# SCH_FirstPCB_2024-05-11.net
KiCad netlist of a schematic drawn in EasyEDA
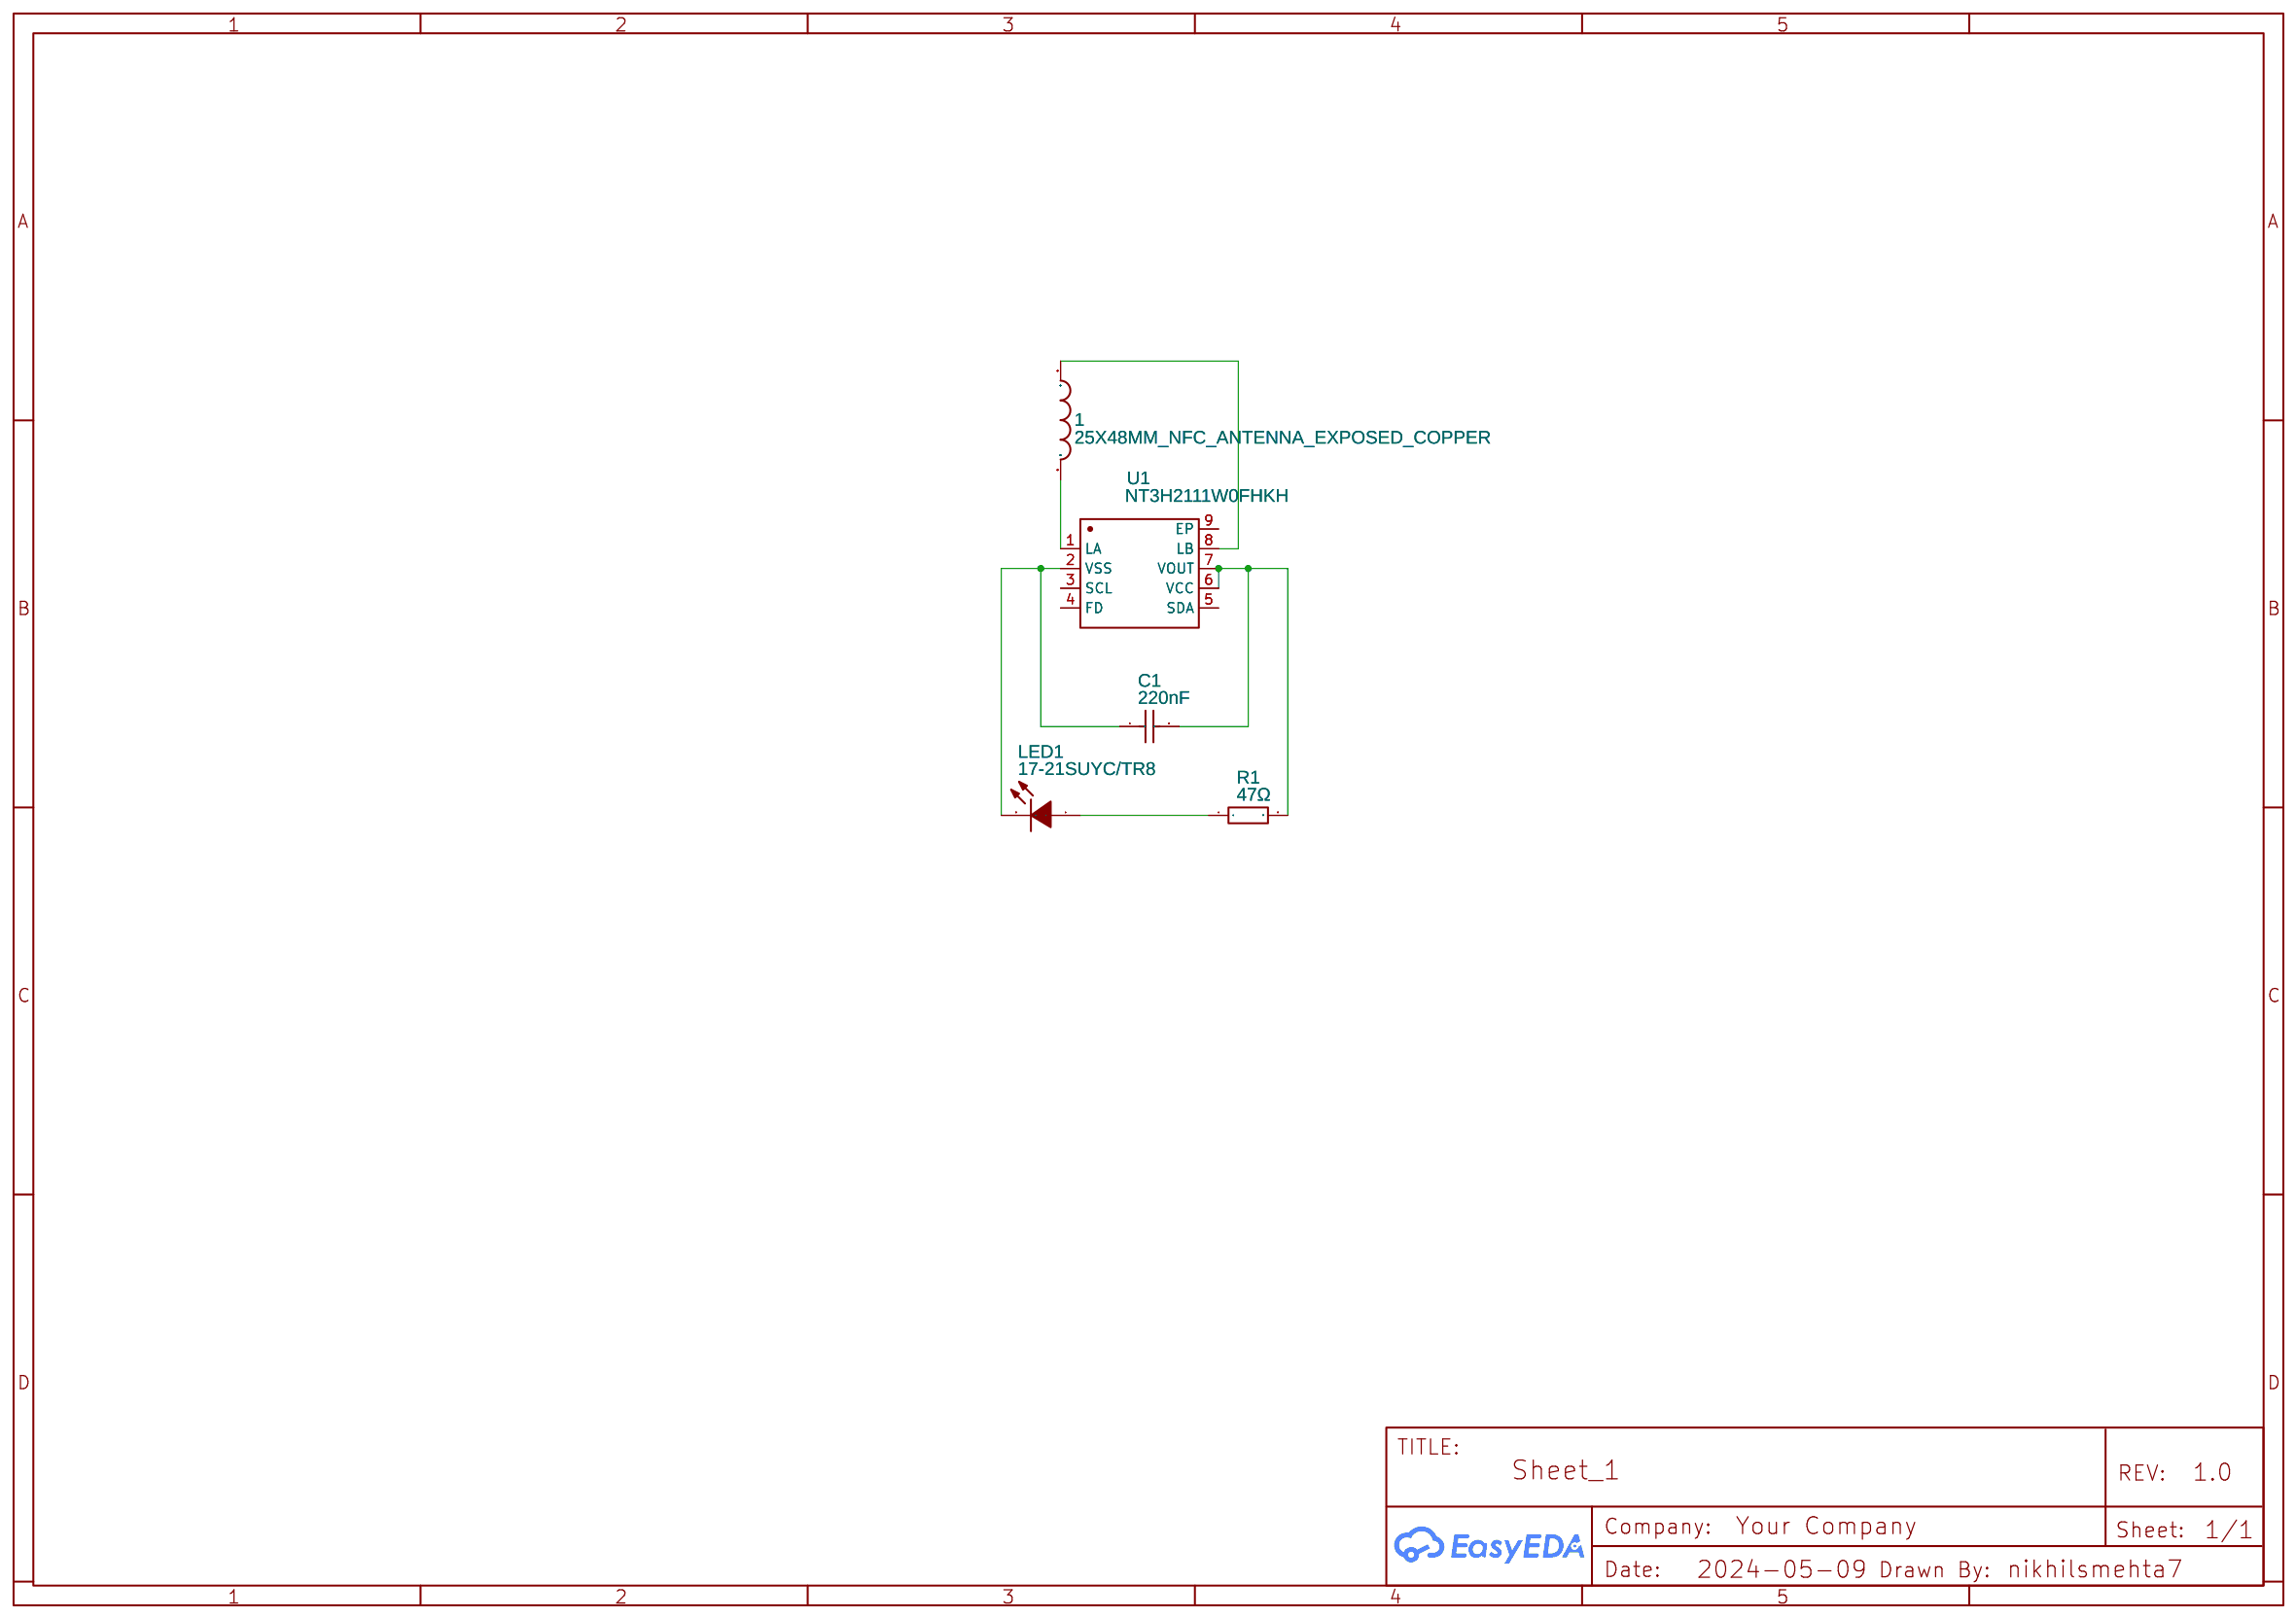
[diagram p0: schematic sheet]

(export (version "E")
  (design (tool "Eeschema 10.0.6"))
  (components
    (comp (ref "1")
      (value "25X48MM_NFC_ANTENNA_EXPOSED_COPPER")
      (libsource (lib "") (part "25X48MM_NFC_ANTENNA_EXPOSED_COPPER"))
    )
    (comp (ref "C1")
      (value "220nF")
      (fields
        (field (name "Manufacturer Part") "CL10B224KA8NNNC")
        (field (name "Manufacturer") "SAMSUNG(三星)")
      )
      (libsource (lib "") (part "CL10B224KA8NNNC"))
    )
    (comp (ref "LED1")
      (value "17-21SUYC/TR8")
      (fields (field (name "Manufacturer Part") "KT-0805黄灯") (field (name "Manufacturer") "KENTO"))
      (libsource (lib "") (part "17-21SUYC/TR8"))
    )
    (comp (ref "R1")
      (value "47Ω")
      (fields
        (field (name "Manufacturer Part") "0603WAF470JT5E")
        (field (name "Manufacturer") "UNI-ROYAL(厚声)")
      )
      (libsource (lib "") (part "0603WAF470JT5E"))
    )
    (comp (ref "U1")
      (value "NT3H2111W0FHKH")
      (fields (field (name "Manufacturer") "NXP(恩智浦)"))
      (libsource (lib "") (part "NT3H2111W0FHKH"))
    )
  )
  (nets
    (net (code "1") (name "Net-(LED1-+)") (class "Default")
      (node (ref "LED1") (pin "1") (pinfunction "+_1") (pintype "unspecified"))
      (node (ref "R1") (pin "1") (pinfunction "1_1") (pintype "input"))
    )
    (net (code "2") (name "Net-(LED1--)") (class "Default")
      (node (ref "C1") (pin "1") (pinfunction "1_1") (pintype "input"))
      (node (ref "LED1") (pin "2") (pinfunction "-_2") (pintype "unspecified"))
      (node (ref "U1") (pin "2") (pinfunction "VSS_2") (pintype "unspecified"))
    )
    (net (code "3") (name "Net-(U1-LA)") (class "Default")
      (node (ref "1") (pin "P$2") (pinfunction "P$2_P$2") (pintype "bidirectional"))
      (node (ref "U1") (pin "1") (pinfunction "LA_1") (pintype "unspecified"))
    )
    (net (code "4") (name "Net-(U1-LB)") (class "Default")
      (node (ref "1") (pin "P$1") (pinfunction "P$1_P$1") (pintype "bidirectional"))
      (node (ref "U1") (pin "8") (pinfunction "LB_8") (pintype "unspecified"))
    )
    (net (code "5") (name "Net-(U1-VCC)") (class "Default")
      (node (ref "C1") (pin "2") (pinfunction "2_2") (pintype "input"))
      (node (ref "R1") (pin "2") (pinfunction "2_2") (pintype "input"))
      (node (ref "U1") (pin "6") (pinfunction "VCC_6") (pintype "unspecified"))
      (node (ref "U1") (pin "7") (pinfunction "VOUT_7") (pintype "unspecified"))
    )
    (net (code "6") (name "unconnected-(U1-EP-Pad9)") (class "Default")
      (node (ref "U1") (pin "9") (pinfunction "EP_9") (pintype "unspecified"))
    )
    (net (code "7") (name "unconnected-(U1-FD-Pad4)") (class "Default")
      (node (ref "U1") (pin "4") (pinfunction "FD_4") (pintype "unspecified"))
    )
    (net (code "8") (name "unconnected-(U1-SCL-Pad3)") (class "Default")
      (node (ref "U1") (pin "3") (pinfunction "SCL_3") (pintype "unspecified"))
    )
    (net (code "9") (name "unconnected-(U1-SDA-Pad5)") (class "Default")
      (node (ref "U1") (pin "5") (pinfunction "SDA_5") (pintype "unspecified"))
    )
  )
)
